# Auxboardone.net
KiCad netlist of a schematic drawn in Altium Designer
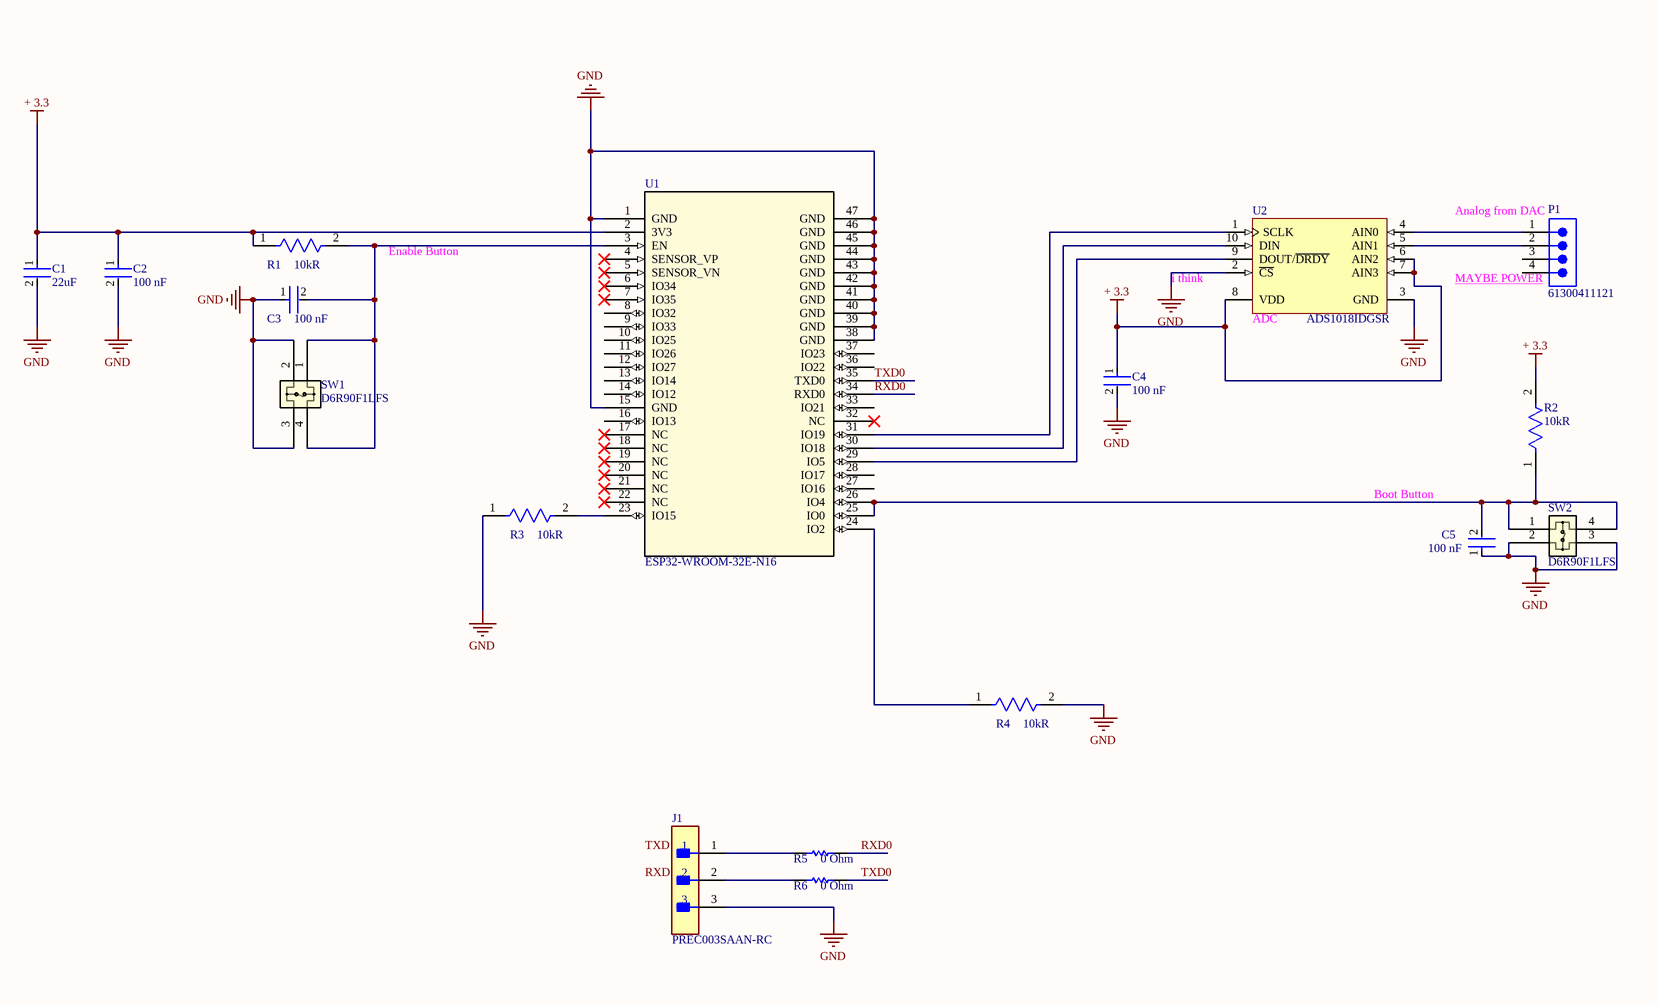
[diagram p0: Auxboardone.SchDoc, right]

(export (version "E")
  (design (tool "Eeschema 10.0.6"))
  (components
    (comp (ref "C1")
      (value "CL21A226MQQNNNE")
      (footprint "FP-CL21-IPC_A")
      (description "CL21 Series 0805 22uF 6.3V ±20% Tolerance X5R Multilayer Ceramic Chip Capacitor")
      (fields (field (name "CAPACITANCE") "22uF") (field (name "TOLERANCE") "20%"))
      (libsource (lib "Altium Content Vault") (part "b4654b650e69147ec39a6b967a45e02"))
    )
    (comp (ref "C2")
      (value "CC0805KRX7R9BB104")
      (footprint "FP-CC0805-0_85-MFG")
      (description "CAP CER 0.1UF 50V X7R 0805")
      (fields
        (field (name "TOLERANCE") "0.1")
        (field (name "CAPACITANCE") "100 nF")
        (field (name "MANUFACTURER") "Yageo")
      )
      (libsource (lib "Altium Content Vault") (part "11868f565c42a9108669ba33697ecf6"))
    )
    (comp (ref "C3")
      (value "CC0805KRX7R9BB104")
      (footprint "FP-CC0805-0_85-MFG")
      (description "CAP CER 0.1UF 50V X7R 0805")
      (fields
        (field (name "TOLERANCE") "0.1")
        (field (name "CAPACITANCE") "100 nF")
        (field (name "MANUFACTURER") "Yageo")
      )
      (libsource (lib "Altium Content Vault") (part "11868f565c42a9108669ba33697ecf6"))
    )
    (comp (ref "C4")
      (value "CC0805KRX7R9BB104")
      (footprint "FP-CC0805-0_85-MFG")
      (description "CAP CER 0.1UF 50V X7R 0805")
      (fields
        (field (name "TOLERANCE") "0.1")
        (field (name "CAPACITANCE") "100 nF")
        (field (name "MANUFACTURER") "Yageo")
      )
      (libsource (lib "Altium Content Vault") (part "11868f565c42a9108669ba33697ecf6"))
    )
    (comp (ref "C5")
      (value "CC0805KRX7R9BB104")
      (footprint "FP-CC0805-0_85-MFG")
      (description "CAP CER 0.1UF 50V X7R 0805")
      (fields
        (field (name "TOLERANCE") "0.1")
        (field (name "CAPACITANCE") "100 nF")
        (field (name "MANUFACTURER") "Yageo")
      )
      (libsource (lib "Altium Content Vault") (part "11868f565c42a9108669ba33697ecf6"))
    )
    (comp (ref "J1")
      (value "PREC003SAAN-RC")
      (footprint "FP-PREC003SAAN-RC-MFG")
      (description "PREC003SAAN-RC Conn Header Vert 3POS 2.54MM")
      (libsource (lib "Altium Content Vault") (part "0d3f023dd272f625e17a2be33dea85f"))
    )
    (comp (ref "P1")
      (value "61300411121")
      (footprint "61300411121")
      (libsource (lib "Altium Content Vault") (part "Header_Male_1R_04P"))
    )
    (comp (ref "R1")
      (value "RR1220P-103-D")
      (footprint "FP-RR1220-IPC_A")
      (description "10kΩ ±0.5% 0.1W 1/10W Chip Resistor 0805 (2012 Metric) Thin Film")
      (fields (field (name "RESISTANCE") "10kR") (field (name "TOLERANCE") "0.5%"))
      (libsource (lib "Altium Content Vault") (part "1029c3af85768c4190bb7ad29bc67b5"))
    )
    (comp (ref "R2")
      (value "RR1220P-103-D")
      (footprint "FP-RR1220-IPC_A")
      (description "10kΩ ±0.5% 0.1W 1/10W Chip Resistor 0805 (2012 Metric) Thin Film")
      (fields (field (name "RESISTANCE") "10kR") (field (name "TOLERANCE") "0.5%"))
      (libsource (lib "Altium Content Vault") (part "1029c3af85768c4190bb7ad29bc67b5"))
    )
    (comp (ref "R3")
      (value "RR1220P-103-D")
      (footprint "FP-RR1220-IPC_A")
      (description "10kΩ ±0.5% 0.1W 1/10W Chip Resistor 0805 (2012 Metric) Thin Film")
      (fields (field (name "RESISTANCE") "10kR") (field (name "TOLERANCE") "0.5%"))
      (libsource (lib "Altium Content Vault") (part "1029c3af85768c4190bb7ad29bc67b5"))
    )
    (comp (ref "R4")
      (value "RR1220P-103-D")
      (footprint "FP-RR1220-IPC_A")
      (description "10kΩ ±0.5% 0.1W 1/10W Chip Resistor 0805 (2012 Metric) Thin Film")
      (fields (field (name "RESISTANCE") "10kR") (field (name "TOLERANCE") "0.5%"))
      (libsource (lib "Altium Content Vault") (part "1029c3af85768c4190bb7ad29bc67b5"))
    )
    (comp (ref "R5")
      (value "ERJ-6GEY0R00V")
      (footprint "RESC2013X70X40NL20T20")
      (description "Chip Resistor, 0 Ohm, +/- 1%, 0.125 W, -55 to 155 degC, 0805 (2012 Metric), RoHS, Tape and Reel")
      (fields (field (name "TOLERANCE") "5%") (field (name "RESISTANCE") "0 Ohm"))
      (libsource (lib "Altium Content Vault") (part "RES-2"))
    )
    (comp (ref "R6")
      (value "ERJ-6GEY0R00V")
      (footprint "RESC2013X70X40NL20T20")
      (description "Chip Resistor, 0 Ohm, +/- 1%, 0.125 W, -55 to 155 degC, 0805 (2012 Metric), RoHS, Tape and Reel")
      (fields (field (name "TOLERANCE") "5%") (field (name "RESISTANCE") "0 Ohm"))
      (libsource (lib "Altium Content Vault") (part "RES-2"))
    )
    (comp (ref "SW1")
      (value "D6R90F1LFS")
      (footprint "D6R_CNK")
      (description "No Description Available")
      (libsource (lib "") (part "D6R90F1LFS_1"))
    )
    (comp (ref "SW2")
      (value "D6R90F1LFS")
      (footprint "D6R_CNK")
      (description "No Description Available")
      (libsource (lib "Button") (part "D6R90F1LFS"))
    )
    (comp (ref "U1")
      (value "ESP32-WROOM-32E-N16")
      (footprint "ESP32-WROOM-32E_EXP")
      (description "No Description Available")
      (libsource (lib "ESP32-WROOM-32E-N16") (part "ESP32-WROOM-32E-N16"))
    )
    (comp (ref "U2")
      (value "ADS1018IDGSR")
      (footprint "TI-DGS10_N")
      (fields (field (name "MANUFACTURER") "Texas Instruments"))
      (libsource (lib "Altium Content Vault") (part "TI-ADS1X18XXX10"))
    )
  )
  (nets
    (net (code "1") (name "+ 3.3") (class "Default")
      (node (ref "C1") (pin "1") (pinfunction "1_1") (pintype "passive"))
      (node (ref "C2") (pin "1") (pinfunction "1_1") (pintype "passive"))
      (node (ref "C4") (pin "1") (pinfunction "1_1") (pintype "passive"))
      (node (ref "R1") (pin "1") (pinfunction "1_1") (pintype "passive"))
      (node (ref "R2") (pin "2") (pinfunction "2_2") (pintype "passive"))
      (node (ref "U1") (pin "2") (pinfunction "3V3_2") (pintype "power_in"))
      (node (ref "U2") (pin "6") (pinfunction "AIN2_6") (pintype "input"))
      (node (ref "U2") (pin "7") (pinfunction "AIN3_7") (pintype "input"))
      (node (ref "U2") (pin "8") (pinfunction "VDD_8") (pintype "power_in"))
    )
    (net (code "3") (name "/RXD0") (class "Default")
      (node (ref "R5") (pin "2") (pinfunction "2_2") (pintype "passive"))
      (node (ref "U1") (pin "34") (pinfunction "RXD0_34") (pintype "bidirectional"))
    )
    (net (code "5") (name "/TXD0") (class "Default")
      (node (ref "R6") (pin "2") (pinfunction "2_2") (pintype "passive"))
      (node (ref "U1") (pin "35") (pinfunction "TXD0_35") (pintype "bidirectional"))
    )
    (net (code "6") (name "GND") (class "Default")
      (node (ref "C1") (pin "2") (pinfunction "2_2") (pintype "passive"))
      (node (ref "C2") (pin "2") (pinfunction "2_2") (pintype "passive"))
      (node (ref "C3") (pin "1") (pinfunction "1_1") (pintype "passive"))
      (node (ref "C4") (pin "2") (pinfunction "2_2") (pintype "passive"))
      (node (ref "C5") (pin "1") (pinfunction "1_1") (pintype "passive"))
      (node (ref "J1") (pin "3") (pinfunction "3_3") (pintype "passive"))
      (node (ref "R3") (pin "1") (pinfunction "1_1") (pintype "passive"))
      (node (ref "R4") (pin "2") (pinfunction "2_2") (pintype "passive"))
      (node (ref "SW1") (pin "2") (pinfunction "2_2") (pintype "passive"))
      (node (ref "SW1") (pin "3") (pinfunction "3_3") (pintype "passive"))
      (node (ref "SW2") (pin "2") (pinfunction "2_2") (pintype "passive"))
      (node (ref "SW2") (pin "3") (pinfunction "3_3") (pintype "passive"))
      (node (ref "U1") (pin "1") (pinfunction "GND_1") (pintype "power_in"))
      (node (ref "U1") (pin "15") (pinfunction "GND_15") (pintype "power_in"))
      (node (ref "U1") (pin "38") (pinfunction "GND_38") (pintype "power_in"))
      (node (ref "U1") (pin "39") (pinfunction "GND_39") (pintype "power_in"))
      (node (ref "U1") (pin "40") (pinfunction "GND_40") (pintype "power_in"))
      (node (ref "U1") (pin "41") (pinfunction "GND_41") (pintype "power_in"))
      (node (ref "U1") (pin "42") (pinfunction "GND_42") (pintype "power_in"))
      (node (ref "U1") (pin "43") (pinfunction "GND_43") (pintype "power_in"))
      (node (ref "U1") (pin "44") (pinfunction "GND_44") (pintype "power_in"))
      (node (ref "U1") (pin "45") (pinfunction "GND_45") (pintype "power_in"))
      (node (ref "U1") (pin "46") (pinfunction "GND_46") (pintype "power_in"))
      (node (ref "U1") (pin "47") (pinfunction "GND_47") (pintype "power_in"))
      (node (ref "U2") (pin "2") (pinfunction "~{CS}_2") (pintype "input"))
      (node (ref "U2") (pin "3") (pinfunction "GND_3") (pintype "power_in"))
    )
    (net (code "7") (name "Net-(J1-Pad1)") (class "Default")
      (node (ref "J1") (pin "1") (pinfunction "1_1") (pintype "passive"))
      (node (ref "R5") (pin "1") (pinfunction "1_1") (pintype "passive"))
    )
    (net (code "8") (name "Net-(J1-Pad2)") (class "Default")
      (node (ref "J1") (pin "2") (pinfunction "2_2") (pintype "passive"))
      (node (ref "R6") (pin "1") (pinfunction "1_1") (pintype "passive"))
    )
    (net (code "9") (name "Net-(U1-EN)") (class "Default")
      (node (ref "C3") (pin "2") (pinfunction "2_2") (pintype "passive"))
      (node (ref "R1") (pin "2") (pinfunction "2_2") (pintype "passive"))
      (node (ref "SW1") (pin "1") (pinfunction "1_1") (pintype "passive"))
      (node (ref "SW1") (pin "4") (pinfunction "4_4") (pintype "passive"))
      (node (ref "U1") (pin "3") (pinfunction "EN_3") (pintype "input"))
    )
    (net (code "10") (name "Net-(U1-IO0)") (class "Default")
      (node (ref "C5") (pin "2") (pinfunction "2_2") (pintype "passive"))
      (node (ref "R2") (pin "1") (pinfunction "1_1") (pintype "passive"))
      (node (ref "SW2") (pin "1") (pinfunction "1_1") (pintype "passive"))
      (node (ref "SW2") (pin "4") (pinfunction "4_4") (pintype "passive"))
      (node (ref "U1") (pin "25") (pinfunction "IO0_25") (pintype "bidirectional"))
      (node (ref "U1") (pin "26") (pinfunction "IO4_26") (pintype "bidirectional"))
    )
    (net (code "11") (name "Net-(U1-IO2)") (class "Default")
      (node (ref "R4") (pin "1") (pinfunction "1_1") (pintype "passive"))
      (node (ref "U1") (pin "24") (pinfunction "IO2_24") (pintype "bidirectional"))
    )
    (net (code "12") (name "Net-(U1-IO5)") (class "Default")
      (node (ref "U1") (pin "29") (pinfunction "IO5_29") (pintype "bidirectional"))
      (node (ref "U2") (pin "9") (pinfunction "DOUT/~{DRDY}_9") (pintype "tri_state"))
    )
    (net (code "13") (name "Net-(U1-IO15)") (class "Default")
      (node (ref "R3") (pin "2") (pinfunction "2_2") (pintype "passive"))
      (node (ref "U1") (pin "23") (pinfunction "IO15_23") (pintype "bidirectional"))
    )
    (net (code "14") (name "Net-(U1-IO18)") (class "Default")
      (node (ref "U1") (pin "30") (pinfunction "IO18_30") (pintype "bidirectional"))
      (node (ref "U2") (pin "10") (pinfunction "DIN_10") (pintype "input"))
    )
    (net (code "15") (name "Net-(U1-IO19)") (class "Default")
      (node (ref "U1") (pin "31") (pinfunction "IO19_31") (pintype "bidirectional"))
      (node (ref "U2") (pin "1") (pinfunction "SCLK_1") (pintype "input"))
    )
    (net (code "16") (name "Net-(U2-AIN0)") (class "Default")
      (node (ref "P1") (pin "1") (pinfunction "1_1") (pintype "passive"))
      (node (ref "U2") (pin "4") (pinfunction "AIN0_4") (pintype "input"))
    )
    (net (code "17") (name "Net-(U2-AIN1)") (class "Default")
      (node (ref "P1") (pin "2") (pinfunction "2_2") (pintype "passive"))
      (node (ref "U2") (pin "5") (pinfunction "AIN1_5") (pintype "input"))
    )
    (net (code "18") (name "unconnected-(P1-Pad3)") (class "Default")
      (node (ref "P1") (pin "3") (pinfunction "3_3") (pintype "passive"))
    )
    (net (code "19") (name "unconnected-(P1-Pad4)") (class "Default")
      (node (ref "P1") (pin "4") (pinfunction "4_4") (pintype "passive"))
    )
    (net (code "20") (name "unconnected-(U1-IO12-Pad14)") (class "Default")
      (node (ref "U1") (pin "14") (pinfunction "IO12_14") (pintype "bidirectional"))
    )
    (net (code "21") (name "unconnected-(U1-IO13-Pad16)") (class "Default")
      (node (ref "U1") (pin "16") (pinfunction "IO13_16") (pintype "bidirectional"))
    )
    (net (code "22") (name "unconnected-(U1-IO14-Pad13)") (class "Default")
      (node (ref "U1") (pin "13") (pinfunction "IO14_13") (pintype "bidirectional"))
    )
    (net (code "23") (name "unconnected-(U1-IO16-Pad27)") (class "Default")
      (node (ref "U1") (pin "27") (pinfunction "IO16_27") (pintype "bidirectional"))
    )
    (net (code "24") (name "unconnected-(U1-IO17-Pad28)") (class "Default")
      (node (ref "U1") (pin "28") (pinfunction "IO17_28") (pintype "bidirectional"))
    )
    (net (code "25") (name "unconnected-(U1-IO21-Pad33)") (class "Default")
      (node (ref "U1") (pin "33") (pinfunction "IO21_33") (pintype "bidirectional"))
    )
    (net (code "26") (name "unconnected-(U1-IO22-Pad36)") (class "Default")
      (node (ref "U1") (pin "36") (pinfunction "IO22_36") (pintype "bidirectional"))
    )
    (net (code "27") (name "unconnected-(U1-IO23-Pad37)") (class "Default")
      (node (ref "U1") (pin "37") (pinfunction "IO23_37") (pintype "bidirectional"))
    )
    (net (code "28") (name "unconnected-(U1-IO25-Pad10)") (class "Default")
      (node (ref "U1") (pin "10") (pinfunction "IO25_10") (pintype "bidirectional"))
    )
    (net (code "29") (name "unconnected-(U1-IO26-Pad11)") (class "Default")
      (node (ref "U1") (pin "11") (pinfunction "IO26_11") (pintype "bidirectional"))
    )
    (net (code "30") (name "unconnected-(U1-IO27-Pad12)") (class "Default")
      (node (ref "U1") (pin "12") (pinfunction "IO27_12") (pintype "bidirectional"))
    )
    (net (code "31") (name "unconnected-(U1-IO32-Pad8)") (class "Default")
      (node (ref "U1") (pin "8") (pinfunction "IO32_8") (pintype "bidirectional"))
    )
    (net (code "32") (name "unconnected-(U1-IO33-Pad9)") (class "Default")
      (node (ref "U1") (pin "9") (pinfunction "IO33_9") (pintype "bidirectional"))
    )
    (net (code "33") (name "unconnected-(U1-IO34-Pad6)") (class "Default")
      (node (ref "U1") (pin "6") (pinfunction "IO34_6") (pintype "input+no_connect"))
    )
    (net (code "34") (name "unconnected-(U1-IO35-Pad7)") (class "Default")
      (node (ref "U1") (pin "7") (pinfunction "IO35_7") (pintype "input+no_connect"))
    )
    (net (code "35") (name "unconnected-(U1-NC-Pad17)") (class "Default")
      (node (ref "U1") (pin "17") (pinfunction "NC_17") (pintype "passive+no_connect"))
    )
    (net (code "36") (name "unconnected-(U1-NC-Pad18)") (class "Default")
      (node (ref "U1") (pin "18") (pinfunction "NC_18") (pintype "passive+no_connect"))
    )
    (net (code "37") (name "unconnected-(U1-NC-Pad19)") (class "Default")
      (node (ref "U1") (pin "19") (pinfunction "NC_19") (pintype "passive+no_connect"))
    )
    (net (code "38") (name "unconnected-(U1-NC-Pad20)") (class "Default")
      (node (ref "U1") (pin "20") (pinfunction "NC_20") (pintype "passive+no_connect"))
    )
    (net (code "39") (name "unconnected-(U1-NC-Pad21)") (class "Default")
      (node (ref "U1") (pin "21") (pinfunction "NC_21") (pintype "passive+no_connect"))
    )
    (net (code "40") (name "unconnected-(U1-NC-Pad22)") (class "Default")
      (node (ref "U1") (pin "22") (pinfunction "NC_22") (pintype "passive+no_connect"))
    )
    (net (code "41") (name "unconnected-(U1-NC-Pad32)") (class "Default")
      (node (ref "U1") (pin "32") (pinfunction "NC_32") (pintype "passive+no_connect"))
    )
    (net (code "42") (name "unconnected-(U1-SENSOR_VN-Pad5)") (class "Default")
      (node (ref "U1") (pin "5") (pinfunction "SENSOR_VN_5") (pintype "input+no_connect"))
    )
    (net (code "43") (name "unconnected-(U1-SENSOR_VP-Pad4)") (class "Default")
      (node (ref "U1") (pin "4") (pinfunction "SENSOR_VP_4") (pintype "input+no_connect"))
    )
  )
)
